# midi-in.net
KiCad netlist of a schematic drawn in EAGLE
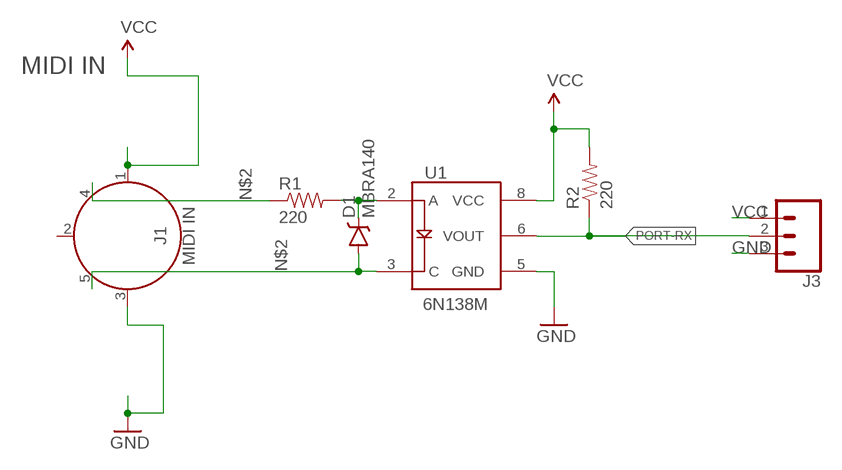
[diagram p0: schematic, sheet 1]

(export (version "E")
  (design (tool "Eeschema 10.0.6"))
  (components
    (comp (ref "D1")
      (value "MBRA140")
      (footprint "eagle-import:SMA-DIODE")
      (libsource (lib "eagle-import") (part "MBRA140"))
    )
    (comp (ref "J1")
      (value "MIDI IN")
      (footprint "eagle-import:5-PIN-DIN-RA-PCB-NEW")
      (libsource (lib "eagle-import") (part "5-PIN-CIRCULAR-DINNEW"))
    )
    (comp (ref "J3")
      (value "CONN_03")
      (footprint "eagle-import:1X03")
      (libsource (lib "eagle-import") (part "CONN_03"))
    )
    (comp (ref "R1")
      (value "220")
      (footprint "eagle-import:0603-RES")
      (libsource (lib "eagle-import") (part "220OHM-1/10W-1%(0603)"))
    )
    (comp (ref "R2")
      (value "220")
      (footprint "eagle-import:0603-RES")
      (libsource (lib "eagle-import") (part "220OHM-1/10W-1%(0603)"))
    )
    (comp (ref "U1")
      (value "6N138M")
      (footprint "eagle-import:8-SMD")
      (libsource (lib "eagle-import") (part "OPTO_DARL_6N138S"))
    )
  )
  (nets
    (net (code "1") (name "/N$2") (class "Default")
      (node (ref "J1") (pin "4") (pinfunction "4_4") (pintype "bidirectional"))
      (node (ref "R1") (pin "1") (pinfunction "1_1") (pintype "passive"))
    )
    (net (code "2") (name "GND") (class "Default")
      (node (ref "J1") (pin "3") (pinfunction "3_3") (pintype "bidirectional"))
      (node (ref "J3") (pin "3") (pinfunction "3_3") (pintype "passive"))
      (node (ref "U1") (pin "5") (pinfunction "GND_5") (pintype "bidirectional"))
    )
    (net (code "3") (name "Net-(U1-A)") (class "Default")
      (node (ref "D1") (pin "C") (pinfunction "C_C") (pintype "passive"))
      (node (ref "R1") (pin "2") (pinfunction "2_2") (pintype "passive"))
      (node (ref "U1") (pin "2") (pinfunction "A_2") (pintype "bidirectional"))
    )
    (net (code "4") (name "Net-(U1-C)") (class "Default")
      (node (ref "D1") (pin "A") (pinfunction "A_A") (pintype "passive"))
      (node (ref "J1") (pin "5") (pinfunction "5_5") (pintype "bidirectional"))
      (node (ref "U1") (pin "3") (pinfunction "C_3") (pintype "bidirectional"))
    )
    (net (code "5") (name "PORT-RX") (class "Default")
      (node (ref "J3") (pin "2") (pinfunction "2_2") (pintype "passive"))
      (node (ref "R2") (pin "1") (pinfunction "1_1") (pintype "passive"))
      (node (ref "U1") (pin "6") (pinfunction "VOUT_6") (pintype "bidirectional"))
    )
    (net (code "6") (name "VCC") (class "Default")
      (node (ref "J1") (pin "1") (pinfunction "1_1") (pintype "bidirectional"))
      (node (ref "J3") (pin "1") (pinfunction "1_1") (pintype "passive"))
      (node (ref "R2") (pin "2") (pinfunction "2_2") (pintype "passive"))
      (node (ref "U1") (pin "8") (pinfunction "VCC_8") (pintype "bidirectional"))
    )
    (net (code "7") (name "unconnected-(J1-Pad2)") (class "Default")
      (node (ref "J1") (pin "2") (pinfunction "2_2") (pintype "bidirectional"))
    )
  )
)
